# Main.net
KiCad netlist of a schematic drawn in Altium Designer
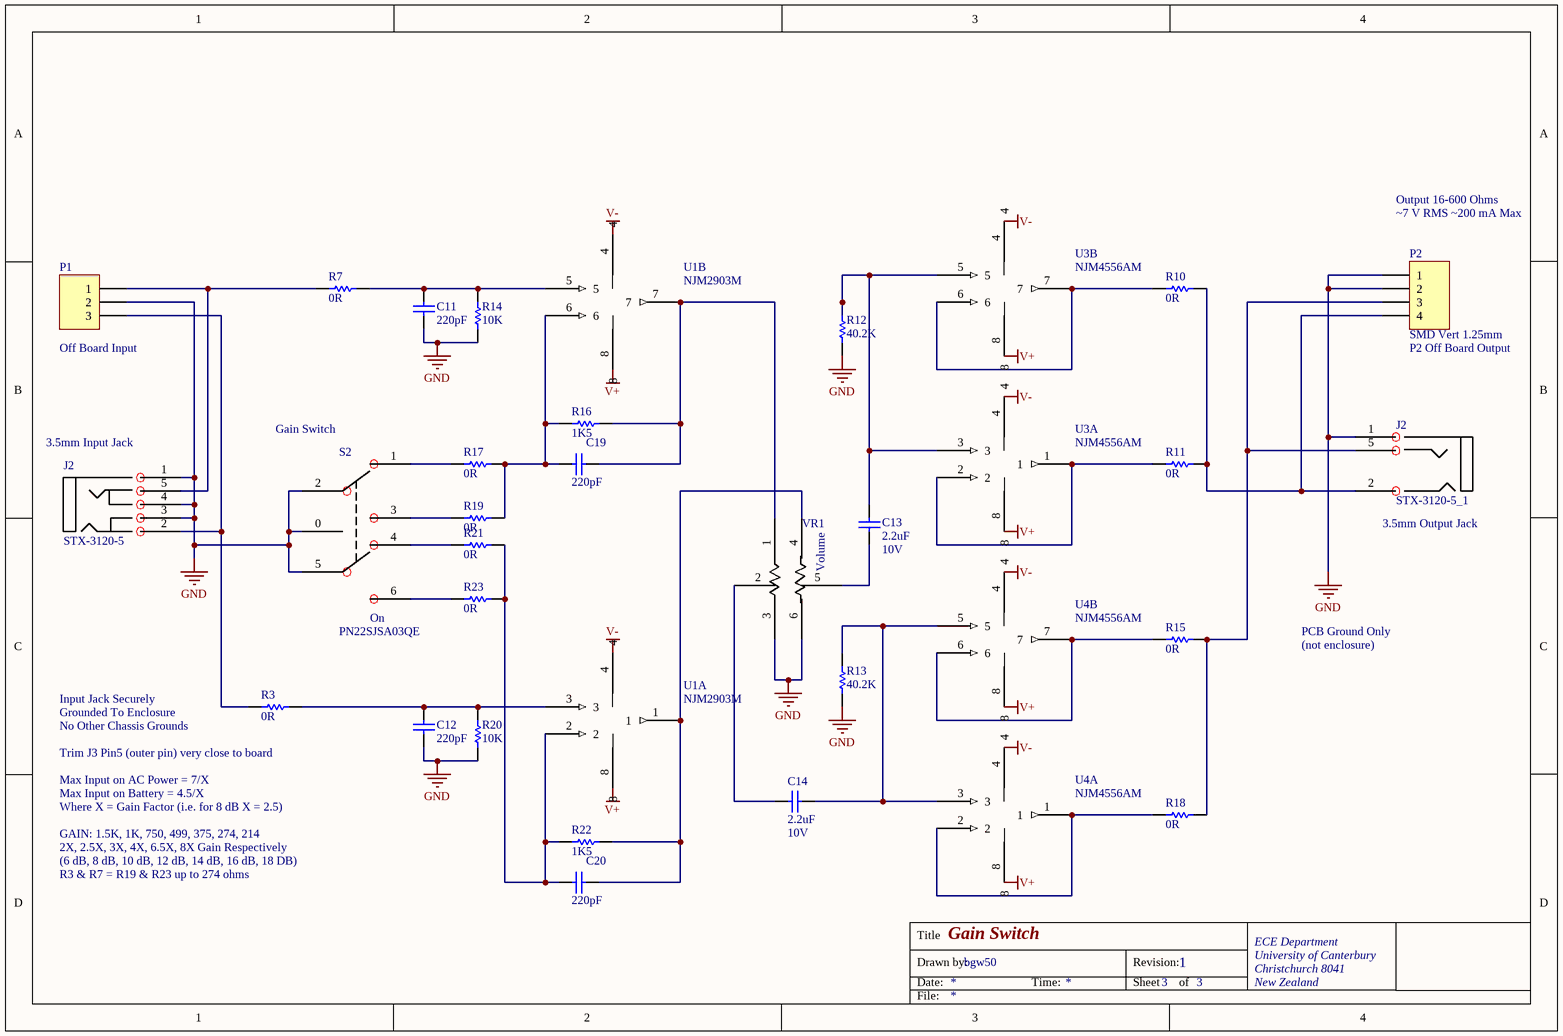
[diagram p0: Main.SchDoc]

(export (version "E")
  (design (tool "Eeschema 10.0.6"))
  (components
    (comp (ref "C11")
      (value "220pF")
      (footprint "CAPC1608L")
      (description "CAP CER 220pF NPO/COG +-5% 50V 0603")
      (libsource (lib "ECE Components_16_2") (part "CC_220pF_0603"))
    )
    (comp (ref "C12")
      (value "220pF")
      (footprint "CAPC1608L")
      (description "CAP CER 220pF NPO/COG +-5% 50V 0603")
      (libsource (lib "ECE Components_16_2") (part "CC_220pF_0603"))
    )
    (comp (ref "C13")
      (value "2.2uF")
      (footprint "CAPC1608L")
      (description "CAP CER 2.2uF X5R +-20% 10V 0603")
      (fields (field (name "MAX VOLTAGE") "10V"))
      (libsource (lib "ECE Components_16_2") (part "CC_2.2uF_0603"))
    )
    (comp (ref "C14")
      (value "2.2uF")
      (footprint "CAPC1608L")
      (description "CAP CER 2.2uF X5R +-20% 10V 0603")
      (fields (field (name "MAX VOLTAGE") "10V"))
      (libsource (lib "ECE Components_16_2") (part "CC_2.2uF_0603"))
    )
    (comp (ref "C19")
      (value "220pF")
      (footprint "CAPC1608L")
      (description "CAP CER 220pF NPO/COG +-5% 50V 0603")
      (libsource (lib "ECE Components_16_2") (part "CC_220pF_0603"))
    )
    (comp (ref "C20")
      (value "220pF")
      (footprint "CAPC1608L")
      (description "CAP CER 220pF NPO/COG +-5% 50V 0603")
      (libsource (lib "ECE Components_16_2") (part "CC_220pF_0603"))
    )
    (comp (ref "J2") (value "STX-3120-5_1") (libsource (lib "Schlib1") (part "STX-3120-5_1")))
    (comp (ref "P1")
      (value "SMD Horiz 1.25mm")
      (footprint "SD-53261-0319")
      (description "Header_Horiz_3Pos_1.25mm_125V@1A_SMT")
      (fields (field (name "MANUFACTURER") "Molex") (field (name "MANUFACTURER PART NUMBER") "53261-0390"))
      (libsource (lib "ECE Components_16_2") (part "JB_53261-03"))
    )
    (comp (ref "P2")
      (value "SMD Vert 1.25mm")
      (footprint "SD-53398-0419")
      (description "Header_Vert_4Pos_1.25mm_125V@1A_SMT")
      (fields (field (name "MANUFACTURER") "MOLEX") (field (name "MANUFACTURER PART NUMBER") "53398-0471"))
      (libsource (lib "ECE Components_16_2") (part "JB_53398-04"))
    )
    (comp (ref "R3")
      (value "0R")
      (footprint "RESC1608L")
      (description "RES 0.0 OHM 1/10W 5% 0603 SMD")
      (libsource (lib "ECE Components_16_2") (part "RS_0R0"))
    )
    (comp (ref "R7")
      (value "0R")
      (footprint "RESC1608L")
      (description "RES 0.0 OHM 1/10W 5% 0603 SMD")
      (libsource (lib "ECE Components_16_2") (part "RS_0R0"))
    )
    (comp (ref "R10")
      (value "0R")
      (footprint "RESC1608L")
      (description "RES 0.0 OHM 1/10W 5% 0603 SMD")
      (libsource (lib "ECE Components_16_2") (part "RS_0R0"))
    )
    (comp (ref "R11")
      (value "0R")
      (footprint "RESC1608L")
      (description "RES 0.0 OHM 1/10W 5% 0603 SMD")
      (libsource (lib "ECE Components_16_2") (part "RS_0R0"))
    )
    (comp (ref "R12")
      (value "40.2K")
      (footprint "RESC1608L")
      (description "RES 39K OHM 1/10W 5% 0603 SMD")
      (libsource (lib "ECE Components_16_2") (part "RS_39K"))
    )
    (comp (ref "R13")
      (value "40.2K")
      (footprint "RESC1608L")
      (description "RES 39K OHM 1/10W 5% 0603 SMD")
      (libsource (lib "ECE Components_16_2") (part "RS_39K"))
    )
    (comp (ref "R14")
      (value "10K")
      (footprint "RESC1608L")
      (description "RES 10.0K OHM 1/10W 5% 0603 SMD")
      (libsource (lib "ECE Components_16_2") (part "RS_10K"))
    )
    (comp (ref "R15")
      (value "0R")
      (footprint "RESC1608L")
      (description "RES 0.0 OHM 1/10W 5% 0603 SMD")
      (libsource (lib "ECE Components_16_2") (part "RS_0R0"))
    )
    (comp (ref "R16")
      (value "1K5")
      (footprint "RESC1608L")
      (description "RES 1.5K OHM 1/10W 5% 0603 SMD")
      (libsource (lib "ECE Components_16_2") (part "RS_1K5"))
    )
    (comp (ref "R17")
      (value "0R")
      (footprint "RESC1608L")
      (description "RES 0.0 OHM 1/10W 5% 0603 SMD")
      (libsource (lib "ECE Components_16_2") (part "RS_0R0"))
    )
    (comp (ref "R18")
      (value "0R")
      (footprint "RESC1608L")
      (description "RES 0.0 OHM 1/10W 5% 0603 SMD")
      (libsource (lib "ECE Components_16_2") (part "RS_0R0"))
    )
    (comp (ref "R19")
      (value "0R")
      (footprint "RESC1608L")
      (description "RES 0.0 OHM 1/10W 5% 0603 SMD")
      (libsource (lib "ECE Components_16_2") (part "RS_0R0"))
    )
    (comp (ref "R20")
      (value "10K")
      (footprint "RESC1608L")
      (description "RES 10.0K OHM 1/10W 5% 0603 SMD")
      (libsource (lib "ECE Components_16_2") (part "RS_10K"))
    )
    (comp (ref "R21")
      (value "0R")
      (footprint "RESC1608L")
      (description "RES 0.0 OHM 1/10W 5% 0603 SMD")
      (libsource (lib "ECE Components_16_2") (part "RS_0R0"))
    )
    (comp (ref "R22")
      (value "1K5")
      (footprint "RESC1608L")
      (description "RES 1.5K OHM 1/10W 5% 0603 SMD")
      (libsource (lib "ECE Components_16_2") (part "RS_1K5"))
    )
    (comp (ref "R23")
      (value "0R")
      (footprint "RESC1608L")
      (description "RES 0.0 OHM 1/10W 5% 0603 SMD")
      (libsource (lib "ECE Components_16_2") (part "RS_0R0"))
    )
    (comp (ref "S2") (value "PN22SJSA03QE") (libsource (lib "Schlib1") (part "PN22SJSA03QE")))
    (comp (ref "U1") (value "NJM2903M") (footprint "NJM2903M") (libsource (lib "Schlib1") (part "NJM2903D")))
    (comp (ref "U3") (value "NJM4556AM") (footprint "NJM2903M") (libsource (lib "Schlib1") (part "NJM2903D")))
    (comp (ref "U4") (value "NJM4556AM") (footprint "NJM2903M") (libsource (lib "Schlib1") (part "NJM2903D")))
    (comp (ref "VR1") (value "~") (libsource (lib "Schlib1") (part "RK09")))
  )
  (nets
    (net (code "1") (name "GND") (class "Default")
      (node (ref "C11") (pin "1") (pinfunction "1_1") (pintype "passive"))
      (node (ref "C12") (pin "1") (pinfunction "1_1") (pintype "passive"))
      (node (ref "P1") (pin "2") (pinfunction "2_2") (pintype "passive"))
      (node (ref "P2") (pin "1") (pinfunction "1_1") (pintype "passive"))
      (node (ref "P2") (pin "2") (pinfunction "2_2") (pintype "passive"))
      (node (ref "R12") (pin "1") (pinfunction "1_1") (pintype "passive"))
      (node (ref "R13") (pin "1") (pinfunction "1_1") (pintype "passive"))
      (node (ref "R14") (pin "1") (pinfunction "1_1") (pintype "passive"))
      (node (ref "R20") (pin "1") (pinfunction "1_1") (pintype "passive"))
      (node (ref "VR1") (pin "3") (pinfunction "3_3") (pintype "passive"))
      (node (ref "VR1") (pin "6") (pinfunction "6_6") (pintype "passive"))
    )
    (net (code "2") (name "Net-(C11-Pad2)") (class "Default")
      (node (ref "C11") (pin "2") (pinfunction "2_2") (pintype "passive"))
      (node (ref "R14") (pin "2") (pinfunction "2_2") (pintype "passive"))
      (node (ref "R7") (pin "2") (pinfunction "2_2") (pintype "passive"))
      (node (ref "U1") (pin "5") (pinfunction "5_5") (pintype "input"))
    )
    (net (code "3") (name "Net-(C12-Pad2)") (class "Default")
      (node (ref "C12") (pin "2") (pinfunction "2_2") (pintype "passive"))
      (node (ref "R20") (pin "2") (pinfunction "2_2") (pintype "passive"))
      (node (ref "R3") (pin "2") (pinfunction "2_2") (pintype "passive"))
      (node (ref "U1") (pin "3") (pinfunction "3_3") (pintype "input"))
    )
    (net (code "4") (name "Net-(C13-Pad1)") (class "Default")
      (node (ref "C13") (pin "1") (pinfunction "1_1") (pintype "passive"))
      (node (ref "VR1") (pin "5") (pinfunction "5_5") (pintype "passive"))
    )
    (net (code "5") (name "Net-(C13-Pad2)") (class "Default")
      (node (ref "C13") (pin "2") (pinfunction "2_2") (pintype "passive"))
      (node (ref "R12") (pin "2") (pinfunction "2_2") (pintype "passive"))
      (node (ref "U3") (pin "3") (pinfunction "3_3") (pintype "input"))
      (node (ref "U3") (pin "5") (pinfunction "5_5") (pintype "input"))
    )
    (net (code "6") (name "Net-(C14-Pad1)") (class "Default")
      (node (ref "C14") (pin "1") (pinfunction "1_1") (pintype "passive"))
      (node (ref "VR1") (pin "2") (pinfunction "2_2") (pintype "passive"))
    )
    (net (code "7") (name "Net-(C14-Pad2)") (class "Default")
      (node (ref "C14") (pin "2") (pinfunction "2_2") (pintype "passive"))
      (node (ref "R13") (pin "2") (pinfunction "2_2") (pintype "passive"))
      (node (ref "U4") (pin "3") (pinfunction "3_3") (pintype "input"))
      (node (ref "U4") (pin "5") (pinfunction "5_5") (pintype "input"))
    )
    (net (code "8") (name "Net-(C19-Pad1)") (class "Default")
      (node (ref "C19") (pin "1") (pinfunction "1_1") (pintype "passive"))
      (node (ref "R16") (pin "1") (pinfunction "1_1") (pintype "passive"))
      (node (ref "R17") (pin "2") (pinfunction "2_2") (pintype "passive"))
      (node (ref "R19") (pin "2") (pinfunction "2_2") (pintype "passive"))
      (node (ref "U1") (pin "6") (pinfunction "6_6") (pintype "input"))
    )
    (net (code "9") (name "Net-(C19-Pad2)") (class "Default")
      (node (ref "C19") (pin "2") (pinfunction "2_2") (pintype "passive"))
      (node (ref "R16") (pin "2") (pinfunction "2_2") (pintype "passive"))
      (node (ref "U1") (pin "7") (pinfunction "7_7") (pintype "output"))
      (node (ref "VR1") (pin "1") (pinfunction "1_1") (pintype "passive"))
    )
    (net (code "10") (name "Net-(C20-Pad1)") (class "Default")
      (node (ref "C20") (pin "1") (pinfunction "1_1") (pintype "passive"))
      (node (ref "R21") (pin "2") (pinfunction "2_2") (pintype "passive"))
      (node (ref "R22") (pin "1") (pinfunction "1_1") (pintype "passive"))
      (node (ref "R23") (pin "2") (pinfunction "2_2") (pintype "passive"))
      (node (ref "U1") (pin "2") (pinfunction "2_2") (pintype "input"))
    )
    (net (code "11") (name "Net-(C20-Pad2)") (class "Default")
      (node (ref "C20") (pin "2") (pinfunction "2_2") (pintype "passive"))
      (node (ref "R22") (pin "2") (pinfunction "2_2") (pintype "passive"))
      (node (ref "U1") (pin "1") (pinfunction "1_1") (pintype "output"))
      (node (ref "VR1") (pin "4") (pinfunction "4_4") (pintype "passive"))
    )
    (net (code "12") (name "Net-(P1-Pad1)") (class "Default")
      (node (ref "P1") (pin "1") (pinfunction "1_1") (pintype "passive"))
      (node (ref "R7") (pin "1") (pinfunction "1_1") (pintype "passive"))
    )
    (net (code "13") (name "Net-(P1-Pad3)") (class "Default")
      (node (ref "P1") (pin "3") (pinfunction "3_3") (pintype "passive"))
      (node (ref "R3") (pin "1") (pinfunction "1_1") (pintype "passive"))
    )
    (net (code "14") (name "Net-(P2-Pad3)") (class "Default")
      (node (ref "P2") (pin "3") (pinfunction "3_3") (pintype "passive"))
      (node (ref "R15") (pin "2") (pinfunction "2_2") (pintype "passive"))
      (node (ref "R18") (pin "2") (pinfunction "2_2") (pintype "passive"))
    )
    (net (code "15") (name "Net-(P2-Pad4)") (class "Default")
      (node (ref "P2") (pin "4") (pinfunction "4_4") (pintype "passive"))
      (node (ref "R10") (pin "2") (pinfunction "2_2") (pintype "passive"))
      (node (ref "R11") (pin "2") (pinfunction "2_2") (pintype "passive"))
    )
    (net (code "16") (name "Net-(R10-Pad1)") (class "Default")
      (node (ref "R10") (pin "1") (pinfunction "1_1") (pintype "passive"))
      (node (ref "U3") (pin "6") (pinfunction "6_6") (pintype "input"))
      (node (ref "U3") (pin "7") (pinfunction "7_7") (pintype "output"))
    )
    (net (code "17") (name "Net-(R11-Pad1)") (class "Default")
      (node (ref "R11") (pin "1") (pinfunction "1_1") (pintype "passive"))
      (node (ref "U3") (pin "1") (pinfunction "1_1") (pintype "output"))
      (node (ref "U3") (pin "2") (pinfunction "2_2") (pintype "input"))
    )
    (net (code "18") (name "Net-(R15-Pad1)") (class "Default")
      (node (ref "R15") (pin "1") (pinfunction "1_1") (pintype "passive"))
      (node (ref "U4") (pin "6") (pinfunction "6_6") (pintype "input"))
      (node (ref "U4") (pin "7") (pinfunction "7_7") (pintype "output"))
    )
    (net (code "19") (name "Net-(R18-Pad1)") (class "Default")
      (node (ref "R18") (pin "1") (pinfunction "1_1") (pintype "passive"))
      (node (ref "U4") (pin "1") (pinfunction "1_1") (pintype "output"))
      (node (ref "U4") (pin "2") (pinfunction "2_2") (pintype "input"))
    )
    (net (code "22") (name "unconnected-(J2-Pad1)") (class "Default")
      (node (ref "J2") (pin "1") (pinfunction "1_1") (pintype "passive"))
    )
    (net (code "23") (name "unconnected-(J2-Pad1)_1") (class "Default")
      (node (ref "J2") (pin "1") (pinfunction "1_1") (pintype "passive"))
    )
    (net (code "24") (name "unconnected-(J2-Pad2)") (class "Default")
      (node (ref "J2") (pin "2") (pinfunction "2_2") (pintype "passive"))
    )
    (net (code "25") (name "unconnected-(J2-Pad2)_1") (class "Default")
      (node (ref "J2") (pin "2") (pinfunction "2_2") (pintype "passive"))
    )
    (net (code "26") (name "unconnected-(J2-Pad3)") (class "Default")
      (node (ref "J2") (pin "3") (pinfunction "3_3") (pintype "passive"))
    )
    (net (code "27") (name "unconnected-(J2-Pad4)") (class "Default")
      (node (ref "J2") (pin "4") (pinfunction "4_4") (pintype "passive"))
    )
    (net (code "28") (name "unconnected-(J2-Pad5)") (class "Default")
      (node (ref "J2") (pin "5") (pinfunction "5_5") (pintype "passive"))
    )
    (net (code "29") (name "unconnected-(J2-Pad5)_1") (class "Default")
      (node (ref "J2") (pin "5") (pinfunction "5_5") (pintype "passive"))
    )
    (net (code "30") (name "unconnected-(R17-Pad1)") (class "Default")
      (node (ref "R17") (pin "1") (pinfunction "1_1") (pintype "passive"))
    )
    (net (code "31") (name "unconnected-(R19-Pad1)") (class "Default")
      (node (ref "R19") (pin "1") (pinfunction "1_1") (pintype "passive"))
    )
    (net (code "32") (name "unconnected-(R21-Pad1)") (class "Default")
      (node (ref "R21") (pin "1") (pinfunction "1_1") (pintype "passive"))
    )
    (net (code "33") (name "unconnected-(R23-Pad1)") (class "Default")
      (node (ref "R23") (pin "1") (pinfunction "1_1") (pintype "passive"))
    )
    (net (code "34") (name "unconnected-(S2-Pad0)") (class "Default")
      (node (ref "S2") (pin "0") (pinfunction "0_0") (pintype "passive"))
    )
    (net (code "35") (name "unconnected-(S2-Pad1)") (class "Default")
      (node (ref "S2") (pin "1") (pinfunction "1_1") (pintype "passive"))
    )
    (net (code "36") (name "unconnected-(S2-Pad2)") (class "Default")
      (node (ref "S2") (pin "2") (pinfunction "2_2") (pintype "passive"))
    )
    (net (code "37") (name "unconnected-(S2-Pad3)") (class "Default")
      (node (ref "S2") (pin "3") (pinfunction "3_3") (pintype "passive"))
    )
    (net (code "38") (name "unconnected-(S2-Pad4)") (class "Default")
      (node (ref "S2") (pin "4") (pinfunction "4_4") (pintype "passive"))
    )
    (net (code "39") (name "unconnected-(S2-Pad5)") (class "Default")
      (node (ref "S2") (pin "5") (pinfunction "5_5") (pintype "passive"))
    )
    (net (code "40") (name "unconnected-(S2-Pad6)") (class "Default")
      (node (ref "S2") (pin "6") (pinfunction "6_6") (pintype "passive"))
    )
    (net (code "41") (name "unconnected-(U1-Pad4)") (class "Default")
      (node (ref "U1") (pin "4") (pinfunction "4_4") (pintype "passive"))
    )
    (net (code "42") (name "unconnected-(U1-Pad4)_1") (class "Default")
      (node (ref "U1") (pin "4") (pinfunction "4_4") (pintype "passive"))
    )
    (net (code "43") (name "unconnected-(U1-Pad8)") (class "Default")
      (node (ref "U1") (pin "8") (pinfunction "8_8") (pintype "passive"))
    )
    (net (code "44") (name "unconnected-(U1-Pad8)_1") (class "Default")
      (node (ref "U1") (pin "8") (pinfunction "8_8") (pintype "passive"))
    )
    (net (code "45") (name "unconnected-(U3-Pad4)") (class "Default")
      (node (ref "U3") (pin "4") (pinfunction "4_4") (pintype "passive"))
    )
    (net (code "46") (name "unconnected-(U3-Pad4)_1") (class "Default")
      (node (ref "U3") (pin "4") (pinfunction "4_4") (pintype "passive"))
    )
    (net (code "47") (name "unconnected-(U3-Pad8)") (class "Default")
      (node (ref "U3") (pin "8") (pinfunction "8_8") (pintype "passive"))
    )
    (net (code "48") (name "unconnected-(U3-Pad8)_1") (class "Default")
      (node (ref "U3") (pin "8") (pinfunction "8_8") (pintype "passive"))
    )
    (net (code "49") (name "unconnected-(U4-Pad4)") (class "Default")
      (node (ref "U4") (pin "4") (pinfunction "4_4") (pintype "passive"))
    )
    (net (code "50") (name "unconnected-(U4-Pad4)_1") (class "Default")
      (node (ref "U4") (pin "4") (pinfunction "4_4") (pintype "passive"))
    )
    (net (code "51") (name "unconnected-(U4-Pad8)") (class "Default")
      (node (ref "U4") (pin "8") (pinfunction "8_8") (pintype "passive"))
    )
    (net (code "52") (name "unconnected-(U4-Pad8)_1") (class "Default")
      (node (ref "U4") (pin "8") (pinfunction "8_8") (pintype "passive"))
    )
  )
)
